# mcu_io.net
KiCad netlist of a schematic drawn in Altium Designer
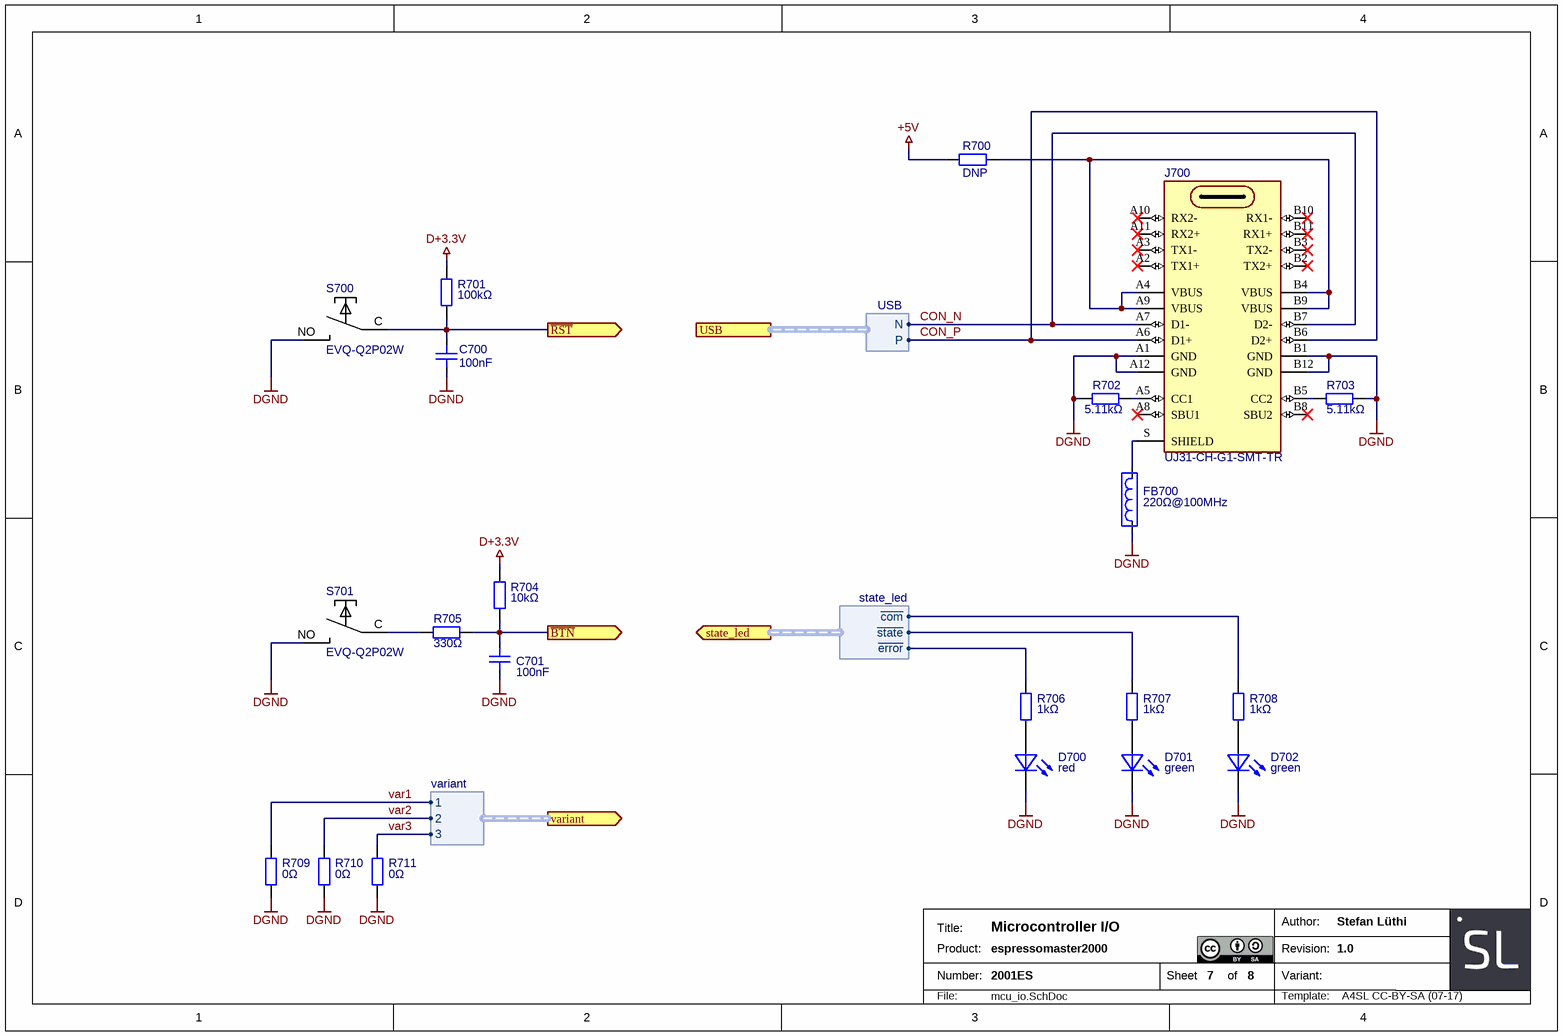
[diagram p0: mcu_io.SchDoc]

(export (version "E")
  (design (tool "Eeschema 10.0.6"))
  (components
    (comp (ref "C700")
      (value "100nF")
      (footprint "SMD0603CAP")
      (description "Ceramic Capacitor")
      (libsource (lib "SL-Library") (part "Capacitor Ceramic"))
    )
    (comp (ref "C701")
      (value "100nF")
      (footprint "SMD0603CAP")
      (description "Ceramic Capacitor")
      (libsource (lib "SL-Library") (part "Capacitor Ceramic"))
    )
    (comp (ref "D700")
      (value "red")
      (footprint "SMD0603LED")
      (description "LED")
      (libsource (lib "SL-Library") (part "LED"))
    )
    (comp (ref "D701")
      (value "green")
      (footprint "SMD0603LED")
      (description "LED")
      (libsource (lib "SL-Library") (part "LED"))
    )
    (comp (ref "D702")
      (value "green")
      (footprint "SMD0603LED")
      (description "LED")
      (libsource (lib "SL-Library") (part "LED"))
    )
    (comp (ref "FB700")
      (value "220Ω@100MHz")
      (footprint "SMD0603RES")
      (description "Ferrite Bead")
      (libsource (lib "SL-Library") (part "Ferrite Bead"))
    )
    (comp (ref "J700")
      (value "UJ31-CH-G1-SMT-TR")
      (footprint "UJ31-CH-G1-SMT-TR")
      (description "USB Type C Jack")
      (libsource (lib "Audio-Streamer") (part "Connector USB C"))
    )
    (comp (ref "R700")
      (value "DNP")
      (footprint "SMD0603RES")
      (description "Resistor")
      (libsource (lib "") (part "Resistor_1"))
    )
    (comp (ref "R701")
      (value "100kΩ")
      (footprint "SMD0603RES")
      (description "Resistor")
      (libsource (lib "SL-Library") (part "Resistor"))
    )
    (comp (ref "R702")
      (value "5.11kΩ")
      (footprint "SMD0603RES")
      (description "Resistor")
      (libsource (lib "") (part "Resistor_1"))
    )
    (comp (ref "R703")
      (value "5.11kΩ")
      (footprint "SMD0603RES")
      (description "Resistor")
      (libsource (lib "Audio-Streamer") (part "Resistor"))
    )
    (comp (ref "R704")
      (value "10kΩ")
      (footprint "SMD0603RES")
      (description "Resistor")
      (libsource (lib "SL-Library") (part "Resistor"))
    )
    (comp (ref "R705")
      (value "330Ω")
      (footprint "SMD0603RES")
      (description "Resistor")
      (libsource (lib "") (part "Resistor_2"))
    )
    (comp (ref "R706")
      (value "1kΩ")
      (footprint "SMD0603RES")
      (description "Resistor")
      (libsource (lib "SL-Library") (part "Resistor"))
    )
    (comp (ref "R707")
      (value "1kΩ")
      (footprint "SMD0603RES")
      (description "Resistor")
      (libsource (lib "SL-Library") (part "Resistor"))
    )
    (comp (ref "R708")
      (value "1kΩ")
      (footprint "SMD0603RES")
      (description "Resistor")
      (libsource (lib "SL-Library") (part "Resistor"))
    )
    (comp (ref "R709")
      (value "0Ω")
      (footprint "SMD0603RES")
      (description "Resistor")
      (libsource (lib "SL-Library") (part "Resistor"))
    )
    (comp (ref "R710")
      (value "0Ω")
      (footprint "SMD0603RES")
      (description "Resistor")
      (libsource (lib "SL-Library") (part "Resistor"))
    )
    (comp (ref "R711")
      (value "0Ω")
      (footprint "SMD0603RES")
      (description "Resistor")
      (libsource (lib "SL-Library") (part "Resistor"))
    )
    (comp (ref "S700")
      (value "EVQ-Q2P02W")
      (footprint "EVQQ2")
      (description "Simple Button")
      (libsource (lib "SL-Library") (part "Button"))
    )
    (comp (ref "S701")
      (value "EVQ-Q2P02W")
      (footprint "EVQQ2")
      (description "Simple Button")
      (libsource (lib "SL-Library") (part "Button"))
    )
  )
  (nets
    (net (code "4") (name "+5V") (class "Default")
      (node (ref "R700") (pin "2") (pinfunction "2_2") (pintype "passive"))
    )
    (net (code "5") (name "/BTN") (class "Default")
      (node (ref "C701") (pin "1") (pinfunction "1_1") (pintype "passive"))
      (node (ref "R704") (pin "1") (pinfunction "1_1") (pintype "passive"))
      (node (ref "R705") (pin "1") (pinfunction "1_1") (pintype "passive"))
    )
    (net (code "6") (name "/CON_N") (class "Default")
      (node (ref "J700") (pin "A7") (pinfunction "D1-_A7") (pintype "bidirectional"))
      (node (ref "J700") (pin "B7") (pinfunction "D2-_B7") (pintype "bidirectional"))
    )
    (net (code "7") (name "/CON_P") (class "Default")
      (node (ref "J700") (pin "A6") (pinfunction "D1+_A6") (pintype "bidirectional"))
      (node (ref "J700") (pin "B6") (pinfunction "D2+_B6") (pintype "bidirectional"))
    )
    (net (code "8") (name "/RST") (class "Default")
      (node (ref "C700") (pin "1") (pinfunction "1_1") (pintype "passive"))
      (node (ref "R701") (pin "1") (pinfunction "1_1") (pintype "passive"))
      (node (ref "S700") (pin "C") (pinfunction "C_C") (pintype "passive"))
    )
    (net (code "9") (name "/var1") (class "Default")
      (node (ref "R709") (pin "2") (pinfunction "2_2") (pintype "passive"))
    )
    (net (code "10") (name "/var2") (class "Default")
      (node (ref "R710") (pin "2") (pinfunction "2_2") (pintype "passive"))
    )
    (net (code "11") (name "/var3") (class "Default")
      (node (ref "R711") (pin "2") (pinfunction "2_2") (pintype "passive"))
    )
    (net (code "15") (name "/~{com}") (class "Default")
      (node (ref "R708") (pin "2") (pinfunction "2_2") (pintype "passive"))
    )
    (net (code "16") (name "/~{error}") (class "Default")
      (node (ref "R706") (pin "2") (pinfunction "2_2") (pintype "passive"))
    )
    (net (code "17") (name "/~{state}") (class "Default")
      (node (ref "R707") (pin "2") (pinfunction "2_2") (pintype "passive"))
    )
    (net (code "18") (name "D+3.3V") (class "Default")
      (node (ref "R701") (pin "2") (pinfunction "2_2") (pintype "passive"))
      (node (ref "R704") (pin "2") (pinfunction "2_2") (pintype "passive"))
    )
    (net (code "19") (name "DGND") (class "Default")
      (node (ref "C700") (pin "2") (pinfunction "2_2") (pintype "passive"))
      (node (ref "C701") (pin "2") (pinfunction "2_2") (pintype "passive"))
      (node (ref "D700") (pin "C") (pinfunction "C_C") (pintype "passive"))
      (node (ref "D701") (pin "C") (pinfunction "C_C") (pintype "passive"))
      (node (ref "D702") (pin "C") (pinfunction "C_C") (pintype "passive"))
      (node (ref "FB700") (pin "1") (pinfunction "1_1") (pintype "passive"))
      (node (ref "J700") (pin "A1") (pinfunction "GND_A1") (pintype "power_in"))
      (node (ref "J700") (pin "A12") (pinfunction "GND_A12") (pintype "power_in"))
      (node (ref "J700") (pin "B1") (pinfunction "GND_B1") (pintype "power_in"))
      (node (ref "J700") (pin "B12") (pinfunction "GND_B12") (pintype "power_in"))
      (node (ref "R702") (pin "1") (pinfunction "1_1") (pintype "passive"))
      (node (ref "R703") (pin "1") (pinfunction "1_1") (pintype "passive"))
      (node (ref "R709") (pin "1") (pinfunction "1_1") (pintype "passive"))
      (node (ref "R710") (pin "1") (pinfunction "1_1") (pintype "passive"))
      (node (ref "R711") (pin "1") (pinfunction "1_1") (pintype "passive"))
      (node (ref "S700") (pin "NO") (pinfunction "NO_NO") (pintype "passive"))
      (node (ref "S701") (pin "NO") (pinfunction "NO_NO") (pintype "passive"))
    )
    (net (code "20") (name "Net-(D700-PadA)") (class "Default")
      (node (ref "D700") (pin "A") (pinfunction "A_A") (pintype "passive"))
      (node (ref "R706") (pin "1") (pinfunction "1_1") (pintype "passive"))
    )
    (net (code "21") (name "Net-(D701-PadA)") (class "Default")
      (node (ref "D701") (pin "A") (pinfunction "A_A") (pintype "passive"))
      (node (ref "R707") (pin "1") (pinfunction "1_1") (pintype "passive"))
    )
    (net (code "22") (name "Net-(D702-PadA)") (class "Default")
      (node (ref "D702") (pin "A") (pinfunction "A_A") (pintype "passive"))
      (node (ref "R708") (pin "1") (pinfunction "1_1") (pintype "passive"))
    )
    (net (code "23") (name "Net-(J700-CC1)") (class "Default")
      (node (ref "J700") (pin "A5") (pinfunction "CC1_A5") (pintype "bidirectional"))
      (node (ref "R702") (pin "2") (pinfunction "2_2") (pintype "passive"))
    )
    (net (code "24") (name "Net-(J700-CC2)") (class "Default")
      (node (ref "J700") (pin "B5") (pinfunction "CC2_B5") (pintype "bidirectional"))
      (node (ref "R703") (pin "2") (pinfunction "2_2") (pintype "passive"))
    )
    (net (code "25") (name "Net-(J700-SHIELD)") (class "Default")
      (node (ref "FB700") (pin "2") (pinfunction "2_2") (pintype "passive"))
      (node (ref "J700") (pin "S") (pinfunction "SHIELD_S") (pintype "power_in"))
    )
    (net (code "26") (name "Net-(J700-VBUS-PadA4)") (class "Default")
      (node (ref "J700") (pin "A4") (pinfunction "VBUS_A4") (pintype "power_in"))
      (node (ref "J700") (pin "A9") (pinfunction "VBUS_A9") (pintype "power_in"))
      (node (ref "J700") (pin "B4") (pinfunction "VBUS_B4") (pintype "power_in"))
      (node (ref "J700") (pin "B9") (pinfunction "VBUS_B9") (pintype "power_in"))
      (node (ref "R700") (pin "1") (pinfunction "1_1") (pintype "passive"))
    )
    (net (code "27") (name "Net-(R705-Pad2)") (class "Default")
      (node (ref "R705") (pin "2") (pinfunction "2_2") (pintype "passive"))
      (node (ref "S701") (pin "C") (pinfunction "C_C") (pintype "passive"))
    )
    (net (code "28") (name "unconnected-(J700-RX1+-PadB11)") (class "Default")
      (node (ref "J700") (pin "B11") (pinfunction "RX1+_B11") (pintype "bidirectional+no_connect"))
    )
    (net (code "29") (name "unconnected-(J700-RX1--PadB10)") (class "Default")
      (node (ref "J700") (pin "B10") (pinfunction "RX1-_B10") (pintype "bidirectional+no_connect"))
    )
    (net (code "30") (name "unconnected-(J700-RX2+-PadA11)") (class "Default")
      (node (ref "J700") (pin "A11") (pinfunction "RX2+_A11") (pintype "bidirectional+no_connect"))
    )
    (net (code "31") (name "unconnected-(J700-RX2--PadA10)") (class "Default")
      (node (ref "J700") (pin "A10") (pinfunction "RX2-_A10") (pintype "bidirectional+no_connect"))
    )
    (net (code "32") (name "unconnected-(J700-SBU1-PadA8)") (class "Default")
      (node (ref "J700") (pin "A8") (pinfunction "SBU1_A8") (pintype "bidirectional+no_connect"))
    )
    (net (code "33") (name "unconnected-(J700-SBU2-PadB8)") (class "Default")
      (node (ref "J700") (pin "B8") (pinfunction "SBU2_B8") (pintype "bidirectional+no_connect"))
    )
    (net (code "34") (name "unconnected-(J700-TX1+-PadA2)") (class "Default")
      (node (ref "J700") (pin "A2") (pinfunction "TX1+_A2") (pintype "bidirectional+no_connect"))
    )
    (net (code "35") (name "unconnected-(J700-TX1--PadA3)") (class "Default")
      (node (ref "J700") (pin "A3") (pinfunction "TX1-_A3") (pintype "bidirectional+no_connect"))
    )
    (net (code "36") (name "unconnected-(J700-TX2+-PadB2)") (class "Default")
      (node (ref "J700") (pin "B2") (pinfunction "TX2+_B2") (pintype "bidirectional+no_connect"))
    )
    (net (code "37") (name "unconnected-(J700-TX2--PadB3)") (class "Default")
      (node (ref "J700") (pin "B3") (pinfunction "TX2-_B3") (pintype "bidirectional+no_connect"))
    )
  )
)
